# SX-Belegt2_10.net
KiCad netlist of a schematic drawn in EAGLE
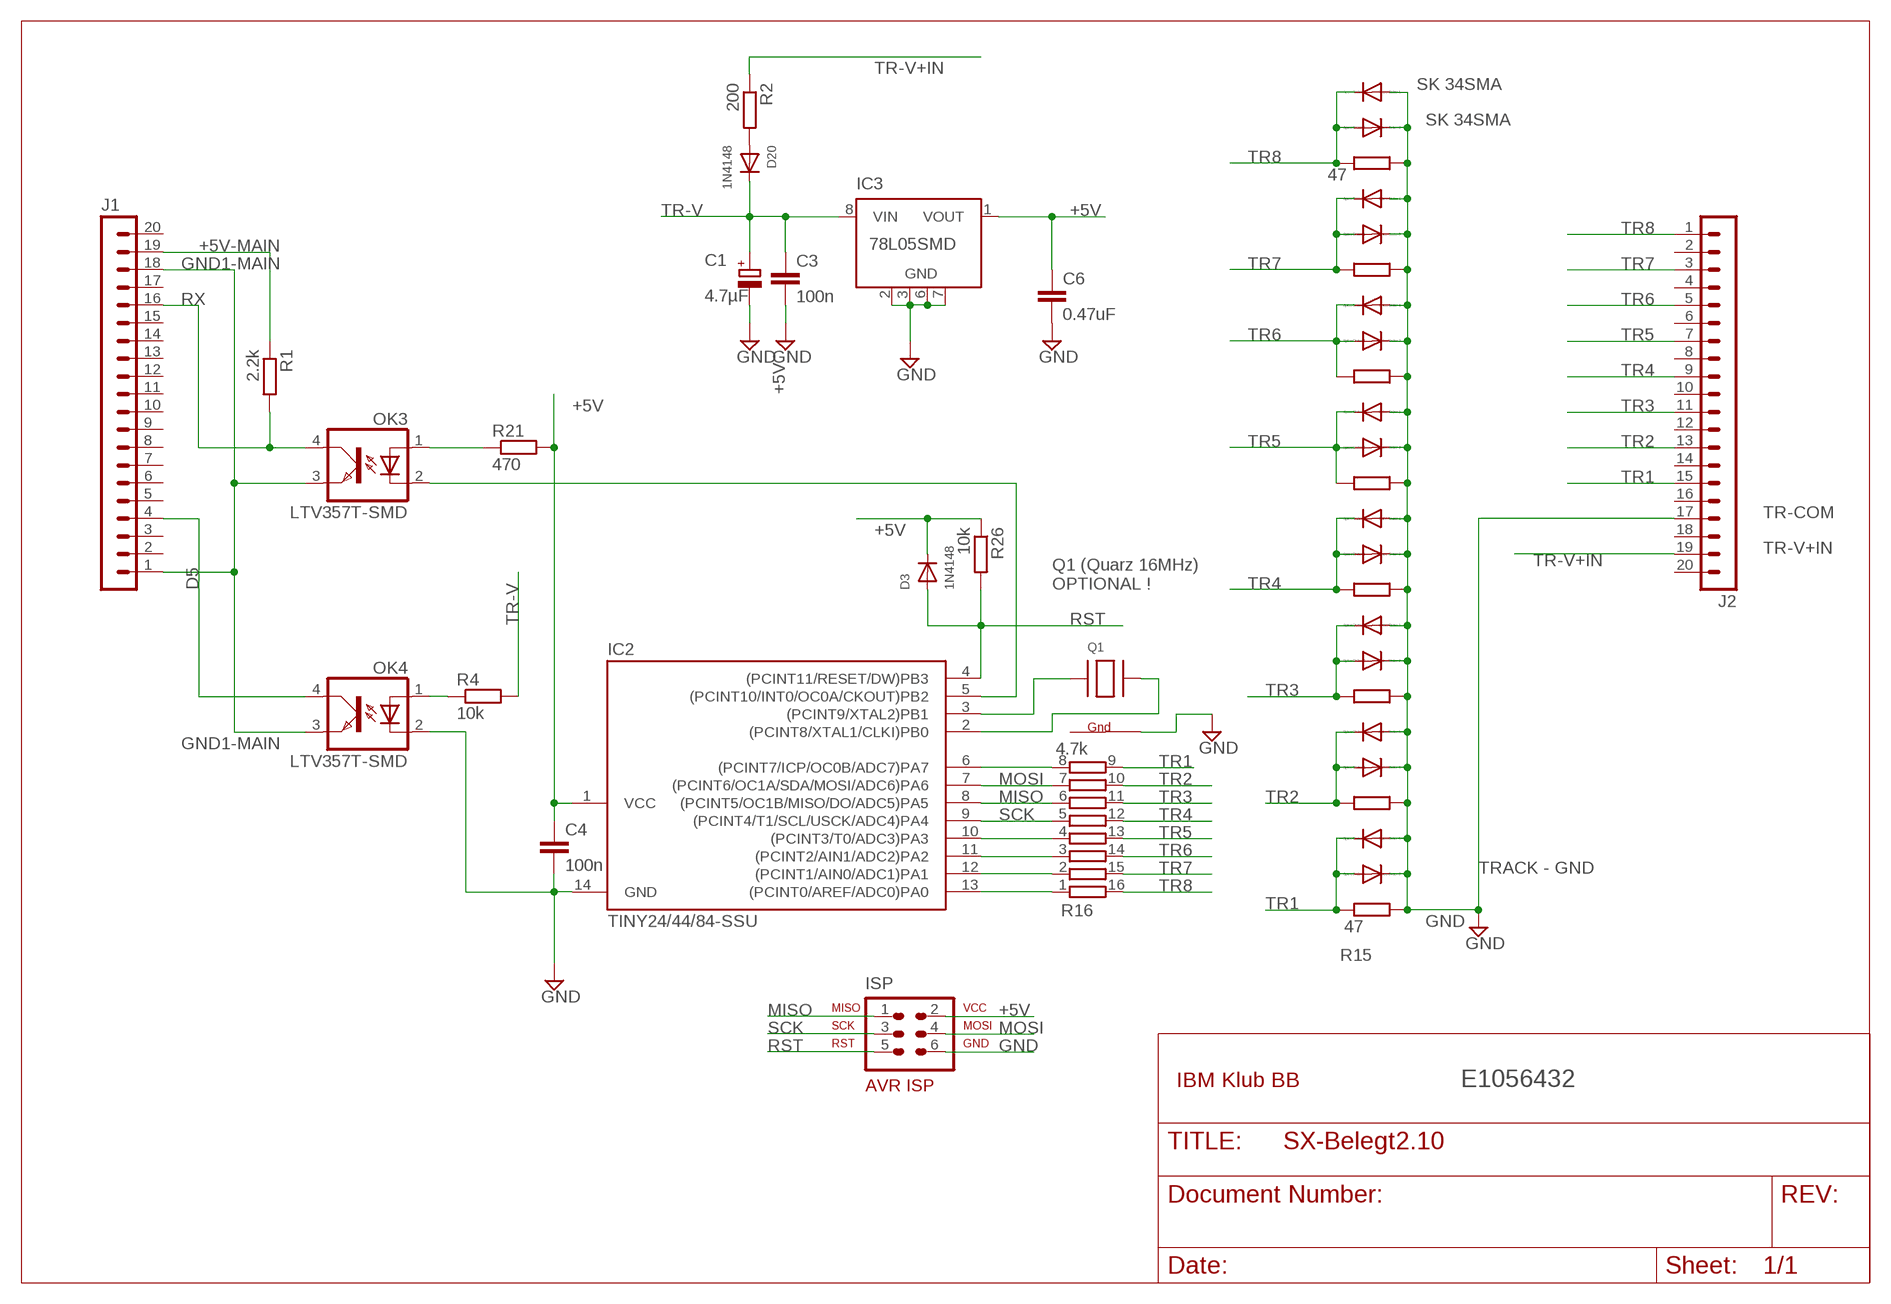
[diagram p0: schematic, sheet 1]

(export (version "E")
  (design (tool "Eeschema 10.0.6"))
  (components
    (comp (ref "C1")
      (value "4.7µF")
      (footprint "eagle-import:SMC_D")
      (libsource (lib "eagle-import") (part "CPOL-EUSMCD"))
    )
    (comp (ref "C3")
      (value "100n")
      (footprint "eagle-import:C0805K")
      (libsource (lib "eagle-import") (part "C-EUC0805K"))
    )
    (comp (ref "C4")
      (value "100n")
      (footprint "eagle-import:C0805K")
      (libsource (lib "eagle-import") (part "C-EUC0805K"))
    )
    (comp (ref "C6")
      (value "0.47uF")
      (footprint "eagle-import:C1206")
      (libsource (lib "eagle-import") (part "C-EUC1206"))
    )
    (comp (ref "D1")
      (value "SK 34SMA")
      (footprint "eagle-import:DO-214AC")
      (libsource (lib "eagle-import") (part "DIODE-DO-214AC"))
    )
    (comp (ref "D2")
      (value "SK 34SMA")
      (footprint "eagle-import:DO-214AC")
      (libsource (lib "eagle-import") (part "DIODE-DO-214AC"))
    )
    (comp (ref "D3")
      (value "1N4148")
      (footprint "eagle-import:SOD-323F")
      (libsource (lib "eagle-import") (part "DIODESOD-323F"))
    )
    (comp (ref "D4")
      (value "SK 34SMA")
      (footprint "eagle-import:DO-214AC")
      (libsource (lib "eagle-import") (part "DIODE-DO-214AC"))
    )
    (comp (ref "D5")
      (value "SK 34SMA")
      (footprint "eagle-import:DO-214AC")
      (libsource (lib "eagle-import") (part "DIODE-DO-214AC"))
    )
    (comp (ref "D6")
      (value "SK 34SMA")
      (footprint "eagle-import:DO-214AC")
      (libsource (lib "eagle-import") (part "DIODE-DO-214AC"))
    )
    (comp (ref "D7")
      (value "SK 34SMA")
      (footprint "eagle-import:DO-214AC")
      (libsource (lib "eagle-import") (part "DIODE-DO-214AC"))
    )
    (comp (ref "D9")
      (value "SK 34SMA")
      (footprint "eagle-import:DO-214AC")
      (libsource (lib "eagle-import") (part "DIODE-DO-214AC"))
    )
    (comp (ref "D10")
      (value "SK 34SMA")
      (footprint "eagle-import:DO-214AC")
      (libsource (lib "eagle-import") (part "DIODE-DO-214AC"))
    )
    (comp (ref "D11")
      (value "SK 34SMA")
      (footprint "eagle-import:DO-214AC")
      (libsource (lib "eagle-import") (part "DIODE-DO-214AC"))
    )
    (comp (ref "D12")
      (value "SK 34SMA")
      (footprint "eagle-import:DO-214AC")
      (libsource (lib "eagle-import") (part "DIODE-DO-214AC"))
    )
    (comp (ref "D13")
      (value "SK 34SMA")
      (footprint "eagle-import:DO-214AC")
      (libsource (lib "eagle-import") (part "DIODE-DO-214AC"))
    )
    (comp (ref "D15")
      (value "SK 34SMA")
      (footprint "eagle-import:DO-214AC")
      (libsource (lib "eagle-import") (part "DIODE-DO-214AC"))
    )
    (comp (ref "D16")
      (value "SK 34SMA")
      (footprint "eagle-import:DO-214AC")
      (libsource (lib "eagle-import") (part "DIODE-DO-214AC"))
    )
    (comp (ref "D17")
      (value "SK 34SMA")
      (footprint "eagle-import:DO-214AC")
      (libsource (lib "eagle-import") (part "DIODE-DO-214AC"))
    )
    (comp (ref "D18")
      (value "SK 34SMA")
      (footprint "eagle-import:DO-214AC")
      (libsource (lib "eagle-import") (part "DIODE-DO-214AC"))
    )
    (comp (ref "D19")
      (value "SK 34SMA")
      (footprint "eagle-import:DO-214AC")
      (libsource (lib "eagle-import") (part "DIODE-DO-214AC"))
    )
    (comp (ref "D20")
      (value "1N4148")
      (footprint "eagle-import:SOD-323F")
      (libsource (lib "eagle-import") (part "DIODESOD-323F"))
    )
    (comp (ref "IC2")
      (value "TINY24/44/84-SSU")
      (footprint "eagle-import:SOIC14")
      (libsource (lib "eagle-import") (part "TINY24/44/84-SSU"))
    )
    (comp (ref "IC3")
      (value "78L05SMD")
      (footprint "eagle-import:SO08")
      (libsource (lib "eagle-import") (part "78LSMD05"))
    )
    (comp (ref "ISP")
      (value "AVR-ISP-2")
      (footprint "eagle-import:AVR-ISP-6")
      (libsource (lib "eagle-import") (part "AVR-ISP-6VERT"))
    )
    (comp (ref "J1")
      (value "MA20-1")
      (footprint "eagle-import:MA20-1")
      (libsource (lib "eagle-import") (part "MA20-1"))
    )
    (comp (ref "J2")
      (value "MA20-1")
      (footprint "eagle-import:MA20-1")
      (libsource (lib "eagle-import") (part "MA20-1"))
    )
    (comp (ref "OK3")
      (value "LTV357T-SMD")
      (footprint "eagle-import:SMD4")
      (libsource (lib "eagle-import") (part "LTV816S"))
    )
    (comp (ref "OK4")
      (value "LTV357T-SMD")
      (footprint "eagle-import:SMD4")
      (libsource (lib "eagle-import") (part "LTV816S"))
    )
    (comp (ref "Q1")
      (value "XTAL-4-3225")
      (footprint "eagle-import:NX3225")
      (libsource (lib "eagle-import") (part "XTAL-4-3225"))
    )
    (comp (ref "R1")
      (value "2.2k")
      (footprint "eagle-import:R0805W")
      (libsource (lib "eagle-import") (part "R-EU_R0805W"))
    )
    (comp (ref "R2")
      (value "200")
      (footprint "eagle-import:R0805W")
      (libsource (lib "eagle-import") (part "R-EU_R0805W"))
    )
    (comp (ref "R4")
      (value "10k")
      (footprint "eagle-import:R0805W")
      (libsource (lib "eagle-import") (part "R-EU_R0805W"))
    )
    (comp (ref "R5")
      (value "47")
      (footprint "eagle-import:M0805")
      (libsource (lib "eagle-import") (part "R-EU_M0805"))
    )
    (comp (ref "R6")
      (value "47")
      (footprint "eagle-import:M0805")
      (libsource (lib "eagle-import") (part "R-EU_M0805"))
    )
    (comp (ref "R7")
      (value "47")
      (footprint "eagle-import:M0805")
      (libsource (lib "eagle-import") (part "R-EU_M0805"))
    )
    (comp (ref "R11")
      (value "47")
      (footprint "eagle-import:M0805")
      (libsource (lib "eagle-import") (part "R-EU_M0805"))
    )
    (comp (ref "R12")
      (value "47")
      (footprint "eagle-import:M0805")
      (libsource (lib "eagle-import") (part "R-EU_M0805"))
    )
    (comp (ref "R13")
      (value "47")
      (footprint "eagle-import:M0805")
      (libsource (lib "eagle-import") (part "R-EU_M0805"))
    )
    (comp (ref "R14")
      (value "47")
      (footprint "eagle-import:M0805")
      (libsource (lib "eagle-import") (part "R-EU_M0805"))
    )
    (comp (ref "R15")
      (value "47")
      (footprint "eagle-import:M0805")
      (libsource (lib "eagle-import") (part "R-EU_M0805"))
    )
    (comp (ref "R16")
      (value "4.7k")
      (footprint "eagle-import:4816P")
      (fields (field (name "MF") "BOURNS, INC.") (field (name "MPN") "4816P-T01-684LF"))
      (libsource (lib "eagle-import") (part "4816P-T01"))
    )
    (comp (ref "R21")
      (value "470")
      (footprint "eagle-import:R0805W")
      (libsource (lib "eagle-import") (part "R-EU_R0805W"))
    )
    (comp (ref "R26")
      (value "10k")
      (footprint "eagle-import:R0805W")
      (libsource (lib "eagle-import") (part "R-EU_R0805W"))
    )
  )
  (nets
    (net (code "1") (name "/+5V") (class "Default")
      (node (ref "C4") (pin "1") (pinfunction "1_1") (pintype "passive"))
      (node (ref "C6") (pin "1") (pinfunction "1_1") (pintype "passive"))
      (node (ref "D3") (pin "C") (pinfunction "C_C") (pintype "passive"))
      (node (ref "IC2") (pin "1") (pinfunction "VCC_1") (pintype "power_in"))
      (node (ref "IC3") (pin "1") (pinfunction "VOUT_1") (pintype "output"))
      (node (ref "ISP") (pin "2") (pinfunction "2_2") (pintype "passive"))
      (node (ref "R21") (pin "2") (pinfunction "2_2") (pintype "passive"))
      (node (ref "R26") (pin "1") (pinfunction "1_1") (pintype "passive"))
    )
    (net (code "2") (name "/+5V-MAIN") (class "Default")
      (node (ref "J1") (pin "19") (pinfunction "19_19") (pintype "passive"))
      (node (ref "R1") (pin "1") (pinfunction "1_1") (pintype "passive"))
    )
    (net (code "3") (name "/D5") (class "Default")
      (node (ref "J1") (pin "4") (pinfunction "4_4") (pintype "passive"))
      (node (ref "OK4") (pin "4") (pinfunction "COL_4") (pintype "passive"))
    )
    (net (code "4") (name "/G1") (class "Default")
      (node (ref "Q1") (pin "4") (pinfunction "G1_4") (pintype "power_in"))
    )
    (net (code "5") (name "/GND1-MAIN") (class "Default")
      (node (ref "J1") (pin "1") (pinfunction "1_1") (pintype "passive"))
      (node (ref "J1") (pin "18") (pinfunction "18_18") (pintype "passive"))
      (node (ref "OK3") (pin "3") (pinfunction "EMIT_3") (pintype "passive"))
      (node (ref "OK4") (pin "3") (pinfunction "EMIT_3") (pintype "passive"))
    )
    (net (code "6") (name "/MISO") (class "Default")
      (node (ref "IC2") (pin "8") (pinfunction "(PCINT5/OC1B/MISO/DO/ADC5)PA5_8") (pintype "bidirectional"))
      (node (ref "ISP") (pin "1") (pinfunction "1_1") (pintype "passive"))
      (node (ref "R16") (pin "6") (pinfunction "6_6") (pintype "passive"))
    )
    (net (code "7") (name "/MOSI") (class "Default")
      (node (ref "IC2") (pin "7") (pinfunction "(PCINT6/OC1A/SDA/MOSI/ADC6)PA6_7") (pintype "bidirectional"))
      (node (ref "ISP") (pin "4") (pinfunction "4_4") (pintype "passive"))
      (node (ref "R16") (pin "7") (pinfunction "7_7") (pintype "passive"))
    )
    (net (code "8") (name "/RST") (class "Default")
      (node (ref "D3") (pin "A") (pinfunction "A_A") (pintype "passive"))
      (node (ref "IC2") (pin "4") (pinfunction "(PCINT11/RESET/DW)PB3_4") (pintype "bidirectional"))
      (node (ref "ISP") (pin "5") (pinfunction "5_5") (pintype "passive"))
      (node (ref "R26") (pin "2") (pinfunction "2_2") (pintype "passive"))
    )
    (net (code "9") (name "/RX") (class "Default")
      (node (ref "J1") (pin "16") (pinfunction "16_16") (pintype "passive"))
      (node (ref "OK3") (pin "4") (pinfunction "COL_4") (pintype "passive"))
      (node (ref "R1") (pin "2") (pinfunction "2_2") (pintype "passive"))
    )
    (net (code "10") (name "/SCK") (class "Default")
      (node (ref "IC2") (pin "9") (pinfunction "(PCINT4/T1/SCL/USCK/ADC4)PA4_9") (pintype "bidirectional"))
      (node (ref "ISP") (pin "3") (pinfunction "3_3") (pintype "passive"))
      (node (ref "R16") (pin "5") (pinfunction "5_5") (pintype "passive"))
    )
    (net (code "11") (name "/TR-V") (class "Default")
      (node (ref "C1") (pin "+") (pinfunction "+_+") (pintype "passive"))
      (node (ref "C3") (pin "1") (pinfunction "1_1") (pintype "passive"))
      (node (ref "D20") (pin "C") (pinfunction "C_C") (pintype "passive"))
      (node (ref "IC3") (pin "8") (pinfunction "VIN_8") (pintype "passive"))
      (node (ref "R4") (pin "2") (pinfunction "2_2") (pintype "passive"))
    )
    (net (code "12") (name "/TR-V+IN") (class "Default")
      (node (ref "J2") (pin "19") (pinfunction "19_19") (pintype "passive"))
      (node (ref "R2") (pin "1") (pinfunction "1_1") (pintype "passive"))
    )
    (net (code "13") (name "/TR1") (class "Default")
      (node (ref "D13") (pin "C") (pinfunction "C_C") (pintype "passive"))
      (node (ref "D19") (pin "A") (pinfunction "A_A") (pintype "passive"))
      (node (ref "J2") (pin "15") (pinfunction "15_15") (pintype "passive"))
      (node (ref "R15") (pin "2") (pinfunction "2_2") (pintype "passive"))
      (node (ref "R16") (pin "9") (pinfunction "9_9") (pintype "passive"))
    )
    (net (code "14") (name "/TR2") (class "Default")
      (node (ref "D12") (pin "C") (pinfunction "C_C") (pintype "passive"))
      (node (ref "D18") (pin "A") (pinfunction "A_A") (pintype "passive"))
      (node (ref "J2") (pin "13") (pinfunction "13_13") (pintype "passive"))
      (node (ref "R14") (pin "2") (pinfunction "2_2") (pintype "passive"))
      (node (ref "R16") (pin "10") (pinfunction "10_10") (pintype "passive"))
    )
    (net (code "15") (name "/TR3") (class "Default")
      (node (ref "D11") (pin "C") (pinfunction "C_C") (pintype "passive"))
      (node (ref "D17") (pin "A") (pinfunction "A_A") (pintype "passive"))
      (node (ref "J2") (pin "11") (pinfunction "11_11") (pintype "passive"))
      (node (ref "R13") (pin "2") (pinfunction "2_2") (pintype "passive"))
      (node (ref "R16") (pin "11") (pinfunction "11_11") (pintype "passive"))
    )
    (net (code "16") (name "/TR4") (class "Default")
      (node (ref "D10") (pin "C") (pinfunction "C_C") (pintype "passive"))
      (node (ref "D16") (pin "A") (pinfunction "A_A") (pintype "passive"))
      (node (ref "J2") (pin "9") (pinfunction "9_9") (pintype "passive"))
      (node (ref "R12") (pin "2") (pinfunction "2_2") (pintype "passive"))
      (node (ref "R16") (pin "12") (pinfunction "12_12") (pintype "passive"))
    )
    (net (code "17") (name "/TR5") (class "Default")
      (node (ref "D15") (pin "A") (pinfunction "A_A") (pintype "passive"))
      (node (ref "D9") (pin "C") (pinfunction "C_C") (pintype "passive"))
      (node (ref "J2") (pin "7") (pinfunction "7_7") (pintype "passive"))
      (node (ref "R16") (pin "13") (pinfunction "13_13") (pintype "passive"))
      (node (ref "R5") (pin "2") (pinfunction "2_2") (pintype "passive"))
    )
    (net (code "18") (name "/TR6") (class "Default")
      (node (ref "D6") (pin "C") (pinfunction "C_C") (pintype "passive"))
      (node (ref "D7") (pin "A") (pinfunction "A_A") (pintype "passive"))
      (node (ref "J2") (pin "5") (pinfunction "5_5") (pintype "passive"))
      (node (ref "R11") (pin "2") (pinfunction "2_2") (pintype "passive"))
      (node (ref "R16") (pin "14") (pinfunction "14_14") (pintype "passive"))
    )
    (net (code "19") (name "/TR7") (class "Default")
      (node (ref "D4") (pin "C") (pinfunction "C_C") (pintype "passive"))
      (node (ref "D5") (pin "A") (pinfunction "A_A") (pintype "passive"))
      (node (ref "J2") (pin "3") (pinfunction "3_3") (pintype "passive"))
      (node (ref "R16") (pin "15") (pinfunction "15_15") (pintype "passive"))
      (node (ref "R7") (pin "2") (pinfunction "2_2") (pintype "passive"))
    )
    (net (code "20") (name "/TR8") (class "Default")
      (node (ref "D1") (pin "C") (pinfunction "C_C") (pintype "passive"))
      (node (ref "D2") (pin "A") (pinfunction "A_A") (pintype "passive"))
      (node (ref "J2") (pin "1") (pinfunction "1_1") (pintype "passive"))
      (node (ref "R16") (pin "16") (pinfunction "16_16") (pintype "passive"))
      (node (ref "R6") (pin "2") (pinfunction "2_2") (pintype "passive"))
    )
    (net (code "21") (name "GND") (class "Default")
      (node (ref "C1") (pin "-") (pinfunction "-_-") (pintype "passive"))
      (node (ref "C3") (pin "2") (pinfunction "2_2") (pintype "passive"))
      (node (ref "C4") (pin "2") (pinfunction "2_2") (pintype "passive"))
      (node (ref "C6") (pin "2") (pinfunction "2_2") (pintype "passive"))
      (node (ref "D1") (pin "A") (pinfunction "A_A") (pintype "passive"))
      (node (ref "D10") (pin "A") (pinfunction "A_A") (pintype "passive"))
      (node (ref "D11") (pin "A") (pinfunction "A_A") (pintype "passive"))
      (node (ref "D12") (pin "A") (pinfunction "A_A") (pintype "passive"))
      (node (ref "D13") (pin "A") (pinfunction "A_A") (pintype "passive"))
      (node (ref "D15") (pin "C") (pinfunction "C_C") (pintype "passive"))
      (node (ref "D16") (pin "C") (pinfunction "C_C") (pintype "passive"))
      (node (ref "D17") (pin "C") (pinfunction "C_C") (pintype "passive"))
      (node (ref "D18") (pin "C") (pinfunction "C_C") (pintype "passive"))
      (node (ref "D19") (pin "C") (pinfunction "C_C") (pintype "passive"))
      (node (ref "D2") (pin "C") (pinfunction "C_C") (pintype "passive"))
      (node (ref "D4") (pin "A") (pinfunction "A_A") (pintype "passive"))
      (node (ref "D5") (pin "C") (pinfunction "C_C") (pintype "passive"))
      (node (ref "D6") (pin "A") (pinfunction "A_A") (pintype "passive"))
      (node (ref "D7") (pin "C") (pinfunction "C_C") (pintype "passive"))
      (node (ref "D9") (pin "A") (pinfunction "A_A") (pintype "passive"))
      (node (ref "IC2") (pin "14") (pinfunction "GND_14") (pintype "power_in"))
      (node (ref "IC3") (pin "2") (pinfunction "GND_2") (pintype "power_in"))
      (node (ref "IC3") (pin "3") (pinfunction "GND_3") (pintype "power_in"))
      (node (ref "IC3") (pin "6") (pinfunction "GND_6") (pintype "power_in"))
      (node (ref "IC3") (pin "7") (pinfunction "GND_7") (pintype "power_in"))
      (node (ref "ISP") (pin "6") (pinfunction "6_6") (pintype "passive"))
      (node (ref "J2") (pin "17") (pinfunction "17_17") (pintype "passive"))
      (node (ref "OK4") (pin "2") (pinfunction "C_2") (pintype "passive"))
      (node (ref "Q1") (pin "2") (pinfunction "G2_2") (pintype "power_in"))
      (node (ref "R11") (pin "1") (pinfunction "1_1") (pintype "passive"))
      (node (ref "R12") (pin "1") (pinfunction "1_1") (pintype "passive"))
      (node (ref "R13") (pin "1") (pinfunction "1_1") (pintype "passive"))
      (node (ref "R14") (pin "1") (pinfunction "1_1") (pintype "passive"))
      (node (ref "R15") (pin "1") (pinfunction "1_1") (pintype "passive"))
      (node (ref "R5") (pin "1") (pinfunction "1_1") (pintype "passive"))
      (node (ref "R6") (pin "1") (pinfunction "1_1") (pintype "passive"))
      (node (ref "R7") (pin "1") (pinfunction "1_1") (pintype "passive"))
    )
    (net (code "22") (name "Net-(D20-PadA)") (class "Default")
      (node (ref "D20") (pin "A") (pinfunction "A_A") (pintype "passive"))
      (node (ref "R2") (pin "2") (pinfunction "2_2") (pintype "passive"))
    )
    (net (code "23") (name "Net-(IC2-(PCINT0{slash}AREF{slash}ADC0)PA0)") (class "Default")
      (node (ref "IC2") (pin "13") (pinfunction "(PCINT0/AREF/ADC0)PA0_13") (pintype "bidirectional"))
      (node (ref "R16") (pin "1") (pinfunction "1_1") (pintype "passive"))
    )
    (net (code "24") (name "Net-(IC2-(PCINT1{slash}AIN0{slash}ADC1)PA1)") (class "Default")
      (node (ref "IC2") (pin "12") (pinfunction "(PCINT1/AIN0/ADC1)PA1_12") (pintype "bidirectional"))
      (node (ref "R16") (pin "2") (pinfunction "2_2") (pintype "passive"))
    )
    (net (code "25") (name "Net-(IC2-(PCINT2{slash}AIN1{slash}ADC2)PA2)") (class "Default")
      (node (ref "IC2") (pin "11") (pinfunction "(PCINT2/AIN1/ADC2)PA2_11") (pintype "bidirectional"))
      (node (ref "R16") (pin "3") (pinfunction "3_3") (pintype "passive"))
    )
    (net (code "26") (name "Net-(IC2-(PCINT3{slash}T0{slash}ADC3)PA3)") (class "Default")
      (node (ref "IC2") (pin "10") (pinfunction "(PCINT3/T0/ADC3)PA3_10") (pintype "bidirectional"))
      (node (ref "R16") (pin "4") (pinfunction "4_4") (pintype "passive"))
    )
    (net (code "27") (name "Net-(IC2-(PCINT7{slash}ICP{slash}OC0B{slash}ADC7)PA7)") (class "Default")
      (node (ref "IC2") (pin "6") (pinfunction "(PCINT7/ICP/OC0B/ADC7)PA7_6") (pintype "bidirectional"))
      (node (ref "R16") (pin "8") (pinfunction "8_8") (pintype "passive"))
    )
    (net (code "28") (name "Net-(IC2-(PCINT8{slash}XTAL1{slash}CLKI)PB0)") (class "Default")
      (node (ref "IC2") (pin "2") (pinfunction "(PCINT8/XTAL1/CLKI)PB0_2") (pintype "bidirectional"))
      (node (ref "Q1") (pin "3") (pinfunction "X2_3") (pintype "bidirectional"))
    )
    (net (code "29") (name "Net-(IC2-(PCINT9{slash}XTAL2)PB1)") (class "Default")
      (node (ref "IC2") (pin "3") (pinfunction "(PCINT9/XTAL2)PB1_3") (pintype "bidirectional"))
      (node (ref "Q1") (pin "1") (pinfunction "X1_1") (pintype "bidirectional"))
    )
    (net (code "30") (name "Net-(IC2-(PCINT10{slash}INT0{slash}OC0A{slash}CKOUT)PB2)") (class "Default")
      (node (ref "IC2") (pin "5") (pinfunction "(PCINT10/INT0/OC0A/CKOUT)PB2_5") (pintype "bidirectional"))
      (node (ref "OK3") (pin "2") (pinfunction "C_2") (pintype "passive"))
    )
    (net (code "31") (name "Net-(OK3-A)") (class "Default")
      (node (ref "OK3") (pin "1") (pinfunction "A_1") (pintype "passive"))
      (node (ref "R21") (pin "1") (pinfunction "1_1") (pintype "passive"))
    )
    (net (code "32") (name "Net-(OK4-A)") (class "Default")
      (node (ref "OK4") (pin "1") (pinfunction "A_1") (pintype "passive"))
      (node (ref "R4") (pin "1") (pinfunction "1_1") (pintype "passive"))
    )
    (net (code "33") (name "unconnected-(J1-Pad2)") (class "Default")
      (node (ref "J1") (pin "2") (pinfunction "2_2") (pintype "passive"))
    )
    (net (code "34") (name "unconnected-(J1-Pad3)") (class "Default")
      (node (ref "J1") (pin "3") (pinfunction "3_3") (pintype "passive"))
    )
    (net (code "35") (name "unconnected-(J1-Pad5)") (class "Default")
      (node (ref "J1") (pin "5") (pinfunction "5_5") (pintype "passive"))
    )
    (net (code "36") (name "unconnected-(J1-Pad6)") (class "Default")
      (node (ref "J1") (pin "6") (pinfunction "6_6") (pintype "passive"))
    )
    (net (code "37") (name "unconnected-(J1-Pad7)") (class "Default")
      (node (ref "J1") (pin "7") (pinfunction "7_7") (pintype "passive"))
    )
    (net (code "38") (name "unconnected-(J1-Pad8)") (class "Default")
      (node (ref "J1") (pin "8") (pinfunction "8_8") (pintype "passive"))
    )
    (net (code "39") (name "unconnected-(J1-Pad9)") (class "Default")
      (node (ref "J1") (pin "9") (pinfunction "9_9") (pintype "passive"))
    )
    (net (code "40") (name "unconnected-(J1-Pad10)") (class "Default")
      (node (ref "J1") (pin "10") (pinfunction "10_10") (pintype "passive"))
    )
    (net (code "41") (name "unconnected-(J1-Pad11)") (class "Default")
      (node (ref "J1") (pin "11") (pinfunction "11_11") (pintype "passive"))
    )
    (net (code "42") (name "unconnected-(J1-Pad12)") (class "Default")
      (node (ref "J1") (pin "12") (pinfunction "12_12") (pintype "passive"))
    )
    (net (code "43") (name "unconnected-(J1-Pad13)") (class "Default")
      (node (ref "J1") (pin "13") (pinfunction "13_13") (pintype "passive"))
    )
    (net (code "44") (name "unconnected-(J1-Pad14)") (class "Default")
      (node (ref "J1") (pin "14") (pinfunction "14_14") (pintype "passive"))
    )
    (net (code "45") (name "unconnected-(J1-Pad15)") (class "Default")
      (node (ref "J1") (pin "15") (pinfunction "15_15") (pintype "passive"))
    )
    (net (code "46") (name "unconnected-(J1-Pad17)") (class "Default")
      (node (ref "J1") (pin "17") (pinfunction "17_17") (pintype "passive"))
    )
    (net (code "47") (name "unconnected-(J1-Pad20)") (class "Default")
      (node (ref "J1") (pin "20") (pinfunction "20_20") (pintype "passive"))
    )
    (net (code "48") (name "unconnected-(J2-Pad2)") (class "Default")
      (node (ref "J2") (pin "2") (pinfunction "2_2") (pintype "passive"))
    )
    (net (code "49") (name "unconnected-(J2-Pad4)") (class "Default")
      (node (ref "J2") (pin "4") (pinfunction "4_4") (pintype "passive"))
    )
    (net (code "50") (name "unconnected-(J2-Pad6)") (class "Default")
      (node (ref "J2") (pin "6") (pinfunction "6_6") (pintype "passive"))
    )
    (net (code "51") (name "unconnected-(J2-Pad8)") (class "Default")
      (node (ref "J2") (pin "8") (pinfunction "8_8") (pintype "passive"))
    )
    (net (code "52") (name "unconnected-(J2-Pad10)") (class "Default")
      (node (ref "J2") (pin "10") (pinfunction "10_10") (pintype "passive"))
    )
    (net (code "53") (name "unconnected-(J2-Pad12)") (class "Default")
      (node (ref "J2") (pin "12") (pinfunction "12_12") (pintype "passive"))
    )
    (net (code "54") (name "unconnected-(J2-Pad14)") (class "Default")
      (node (ref "J2") (pin "14") (pinfunction "14_14") (pintype "passive"))
    )
    (net (code "55") (name "unconnected-(J2-Pad16)") (class "Default")
      (node (ref "J2") (pin "16") (pinfunction "16_16") (pintype "passive"))
    )
    (net (code "56") (name "unconnected-(J2-Pad18)") (class "Default")
      (node (ref "J2") (pin "18") (pinfunction "18_18") (pintype "passive"))
    )
    (net (code "57") (name "unconnected-(J2-Pad20)") (class "Default")
      (node (ref "J2") (pin "20") (pinfunction "20_20") (pintype "passive"))
    )
  )
)
